# Main_Board.net
KiCad netlist of a schematic drawn in EAGLE
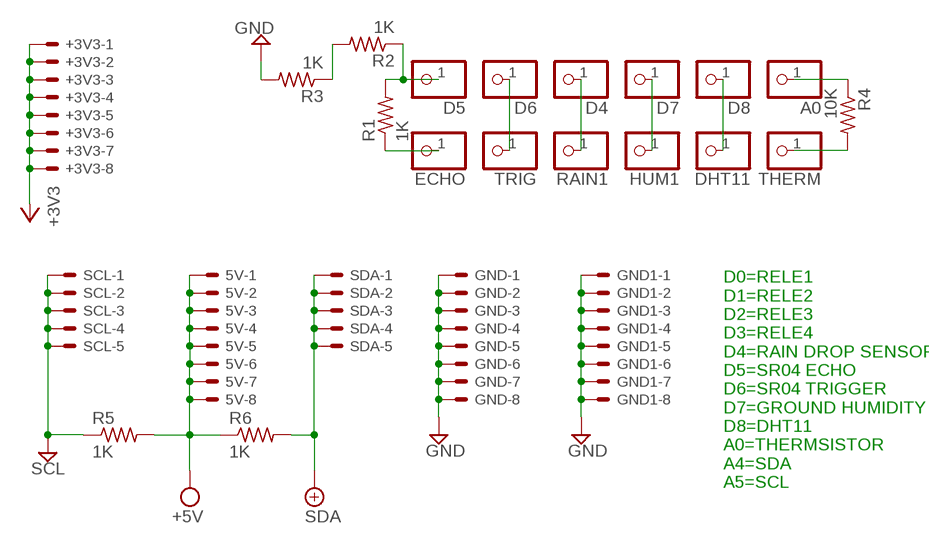
[diagram p0: schematic, sheet 1]

(export (version "E")
  (design (tool "Eeschema 10.0.6"))
  (components
    (comp (ref "+3V3")
      (value "22-23-2081")
      (footprint "eagle-import:22-23-2081")
      (fields (field (name "MF") "MOLEX"))
      (libsource (lib "eagle-import") (part "22-23-2081"))
    )
    (comp (ref "5V")
      (value "22-23-2081")
      (footprint "eagle-import:22-23-2081")
      (fields (field (name "MF") "MOLEX"))
      (libsource (lib "eagle-import") (part "22-23-2081"))
    )
    (comp (ref "A0")
      (value "PINHD-1X1")
      (footprint "eagle-import:1X01")
      (libsource (lib "eagle-import") (part "PINHD-1X1"))
    )
    (comp (ref "D4")
      (value "PINHD-1X1")
      (footprint "eagle-import:1X01")
      (libsource (lib "eagle-import") (part "PINHD-1X1"))
    )
    (comp (ref "D5")
      (value "PINHD-1X1")
      (footprint "eagle-import:1X01")
      (libsource (lib "eagle-import") (part "PINHD-1X1"))
    )
    (comp (ref "D6")
      (value "PINHD-1X1")
      (footprint "eagle-import:1X01")
      (libsource (lib "eagle-import") (part "PINHD-1X1"))
    )
    (comp (ref "D7")
      (value "PINHD-1X1")
      (footprint "eagle-import:1X01")
      (libsource (lib "eagle-import") (part "PINHD-1X1"))
    )
    (comp (ref "D8")
      (value "PINHD-1X1")
      (footprint "eagle-import:1X01")
      (libsource (lib "eagle-import") (part "PINHD-1X1"))
    )
    (comp (ref "DHT11")
      (value "PINHD-1X1")
      (footprint "eagle-import:1X01")
      (libsource (lib "eagle-import") (part "PINHD-1X1"))
    )
    (comp (ref "ECHO")
      (value "PINHD-1X1")
      (footprint "eagle-import:1X01")
      (libsource (lib "eagle-import") (part "PINHD-1X1"))
    )
    (comp (ref "GND")
      (value "22-23-2081")
      (footprint "eagle-import:22-23-2081")
      (fields (field (name "MF") "MOLEX"))
      (libsource (lib "eagle-import") (part "22-23-2081"))
    )
    (comp (ref "GND1")
      (value "22-23-2081")
      (footprint "eagle-import:22-23-2081")
      (fields (field (name "MF") "MOLEX"))
      (libsource (lib "eagle-import") (part "22-23-2081"))
    )
    (comp (ref "HUM1")
      (value "PINHD-1X1")
      (footprint "eagle-import:1X01")
      (libsource (lib "eagle-import") (part "PINHD-1X1"))
    )
    (comp (ref "R1")
      (value "1K")
      (footprint "eagle-import:0204_7")
      (libsource (lib "eagle-import") (part "R-US_0204/7"))
    )
    (comp (ref "R2")
      (value "1K")
      (footprint "eagle-import:0204_7")
      (libsource (lib "eagle-import") (part "R-US_0204/7"))
    )
    (comp (ref "R3")
      (value "1K")
      (footprint "eagle-import:0204_7")
      (libsource (lib "eagle-import") (part "R-US_0204/7"))
    )
    (comp (ref "R4")
      (value "10K")
      (footprint "eagle-import:0204_7")
      (libsource (lib "eagle-import") (part "R-US_0204/7"))
    )
    (comp (ref "R5")
      (value "1K")
      (footprint "eagle-import:0204_7")
      (libsource (lib "eagle-import") (part "R-US_0204/7"))
    )
    (comp (ref "R6")
      (value "1K")
      (footprint "eagle-import:0204_7")
      (libsource (lib "eagle-import") (part "R-US_0204/7"))
    )
    (comp (ref "RAIN1")
      (value "PINHD-1X1")
      (footprint "eagle-import:1X01")
      (libsource (lib "eagle-import") (part "PINHD-1X1"))
    )
    (comp (ref "SCL")
      (value "22-23-2051")
      (footprint "eagle-import:22-23-2051")
      (fields (field (name "MF") "MOLEX"))
      (libsource (lib "eagle-import") (part "22-23-2051"))
    )
    (comp (ref "SDA")
      (value "22-23-2051")
      (footprint "eagle-import:22-23-2051")
      (fields (field (name "MF") "MOLEX"))
      (libsource (lib "eagle-import") (part "22-23-2051"))
    )
    (comp (ref "THERM")
      (value "PINHD-1X1")
      (footprint "eagle-import:1X01")
      (libsource (lib "eagle-import") (part "PINHD-1X1"))
    )
    (comp (ref "TRIG")
      (value "PINHD-1X1")
      (footprint "eagle-import:1X01")
      (libsource (lib "eagle-import") (part "PINHD-1X1"))
    )
  )
  (nets
    (net (code "1") (name "+3V3") (class "Default")
      (node (ref "+3V3") (pin "1") (pinfunction "S_1") (pintype "passive"))
      (node (ref "+3V3") (pin "2") (pinfunction "S_2") (pintype "passive"))
      (node (ref "+3V3") (pin "3") (pinfunction "S_3") (pintype "passive"))
      (node (ref "+3V3") (pin "4") (pinfunction "S_4") (pintype "passive"))
      (node (ref "+3V3") (pin "5") (pinfunction "S_5") (pintype "passive"))
      (node (ref "+3V3") (pin "6") (pinfunction "S_6") (pintype "passive"))
      (node (ref "+3V3") (pin "7") (pinfunction "S_7") (pintype "passive"))
      (node (ref "+3V3") (pin "8") (pinfunction "S_8") (pintype "passive"))
    )
    (net (code "2") (name "+5V") (class "Default")
      (node (ref "5V") (pin "1") (pinfunction "S_1") (pintype "passive"))
      (node (ref "5V") (pin "2") (pinfunction "S_2") (pintype "passive"))
      (node (ref "5V") (pin "3") (pinfunction "S_3") (pintype "passive"))
      (node (ref "5V") (pin "4") (pinfunction "S_4") (pintype "passive"))
      (node (ref "5V") (pin "5") (pinfunction "S_5") (pintype "passive"))
      (node (ref "5V") (pin "6") (pinfunction "S_6") (pintype "passive"))
      (node (ref "5V") (pin "7") (pinfunction "S_7") (pintype "passive"))
      (node (ref "5V") (pin "8") (pinfunction "S_8") (pintype "passive"))
      (node (ref "R5") (pin "2") (pinfunction "2_2") (pintype "passive"))
      (node (ref "R6") (pin "1") (pinfunction "1_1") (pintype "passive"))
    )
    (net (code "3") (name "GND") (class "Default")
      (node (ref "GND") (pin "1") (pinfunction "S_1") (pintype "passive"))
      (node (ref "GND") (pin "2") (pinfunction "S_2") (pintype "passive"))
      (node (ref "GND") (pin "3") (pinfunction "S_3") (pintype "passive"))
      (node (ref "GND") (pin "4") (pinfunction "S_4") (pintype "passive"))
      (node (ref "GND") (pin "5") (pinfunction "S_5") (pintype "passive"))
      (node (ref "GND") (pin "6") (pinfunction "S_6") (pintype "passive"))
      (node (ref "GND") (pin "7") (pinfunction "S_7") (pintype "passive"))
      (node (ref "GND") (pin "8") (pinfunction "S_8") (pintype "passive"))
      (node (ref "GND1") (pin "1") (pinfunction "S_1") (pintype "passive"))
      (node (ref "GND1") (pin "2") (pinfunction "S_2") (pintype "passive"))
      (node (ref "GND1") (pin "3") (pinfunction "S_3") (pintype "passive"))
      (node (ref "GND1") (pin "4") (pinfunction "S_4") (pintype "passive"))
      (node (ref "GND1") (pin "5") (pinfunction "S_5") (pintype "passive"))
      (node (ref "GND1") (pin "6") (pinfunction "S_6") (pintype "passive"))
      (node (ref "GND1") (pin "7") (pinfunction "S_7") (pintype "passive"))
      (node (ref "GND1") (pin "8") (pinfunction "S_8") (pintype "passive"))
      (node (ref "R3") (pin "2") (pinfunction "2_2") (pintype "passive"))
    )
    (net (code "4") (name "Net-(A0-Pad1)") (class "Default")
      (node (ref "A0") (pin "1") (pinfunction "1_1") (pintype "passive"))
      (node (ref "R4") (pin "1") (pinfunction "1_1") (pintype "passive"))
    )
    (net (code "5") (name "Net-(D4-Pad1)") (class "Default")
      (node (ref "D4") (pin "1") (pinfunction "1_1") (pintype "passive"))
      (node (ref "RAIN1") (pin "1") (pinfunction "1_1") (pintype "passive"))
    )
    (net (code "6") (name "Net-(D5-Pad1)") (class "Default")
      (node (ref "D5") (pin "1") (pinfunction "1_1") (pintype "passive"))
      (node (ref "R1") (pin "2") (pinfunction "2_2") (pintype "passive"))
      (node (ref "R2") (pin "1") (pinfunction "1_1") (pintype "passive"))
    )
    (net (code "7") (name "Net-(D6-Pad1)") (class "Default")
      (node (ref "D6") (pin "1") (pinfunction "1_1") (pintype "passive"))
      (node (ref "TRIG") (pin "1") (pinfunction "1_1") (pintype "passive"))
    )
    (net (code "8") (name "Net-(D7-Pad1)") (class "Default")
      (node (ref "D7") (pin "1") (pinfunction "1_1") (pintype "passive"))
      (node (ref "HUM1") (pin "1") (pinfunction "1_1") (pintype "passive"))
    )
    (net (code "9") (name "Net-(D8-Pad1)") (class "Default")
      (node (ref "D8") (pin "1") (pinfunction "1_1") (pintype "passive"))
      (node (ref "DHT11") (pin "1") (pinfunction "1_1") (pintype "passive"))
    )
    (net (code "10") (name "Net-(ECHO-Pad1)") (class "Default")
      (node (ref "ECHO") (pin "1") (pinfunction "1_1") (pintype "passive"))
      (node (ref "R1") (pin "1") (pinfunction "1_1") (pintype "passive"))
    )
    (net (code "11") (name "Net-(R2-Pad2)") (class "Default")
      (node (ref "R2") (pin "2") (pinfunction "2_2") (pintype "passive"))
      (node (ref "R3") (pin "1") (pinfunction "1_1") (pintype "passive"))
    )
    (net (code "12") (name "Net-(R4-Pad2)") (class "Default")
      (node (ref "R4") (pin "2") (pinfunction "2_2") (pintype "passive"))
      (node (ref "THERM") (pin "1") (pinfunction "1_1") (pintype "passive"))
    )
    (net (code "13") (name "SCL") (class "Default")
      (node (ref "R5") (pin "1") (pinfunction "1_1") (pintype "passive"))
      (node (ref "SCL") (pin "1") (pinfunction "S_1") (pintype "passive"))
      (node (ref "SCL") (pin "2") (pinfunction "S_2") (pintype "passive"))
      (node (ref "SCL") (pin "3") (pinfunction "S_3") (pintype "passive"))
      (node (ref "SCL") (pin "4") (pinfunction "S_4") (pintype "passive"))
      (node (ref "SCL") (pin "5") (pinfunction "S_5") (pintype "passive"))
    )
    (net (code "14") (name "SDA") (class "Default")
      (node (ref "R6") (pin "2") (pinfunction "2_2") (pintype "passive"))
      (node (ref "SDA") (pin "1") (pinfunction "S_1") (pintype "passive"))
      (node (ref "SDA") (pin "2") (pinfunction "S_2") (pintype "passive"))
      (node (ref "SDA") (pin "3") (pinfunction "S_3") (pintype "passive"))
      (node (ref "SDA") (pin "4") (pinfunction "S_4") (pintype "passive"))
      (node (ref "SDA") (pin "5") (pinfunction "S_5") (pintype "passive"))
    )
  )
)
